# Patch_panel_module_-_CAT6_daughter_board.net
KiCad netlist of a schematic drawn in EAGLE
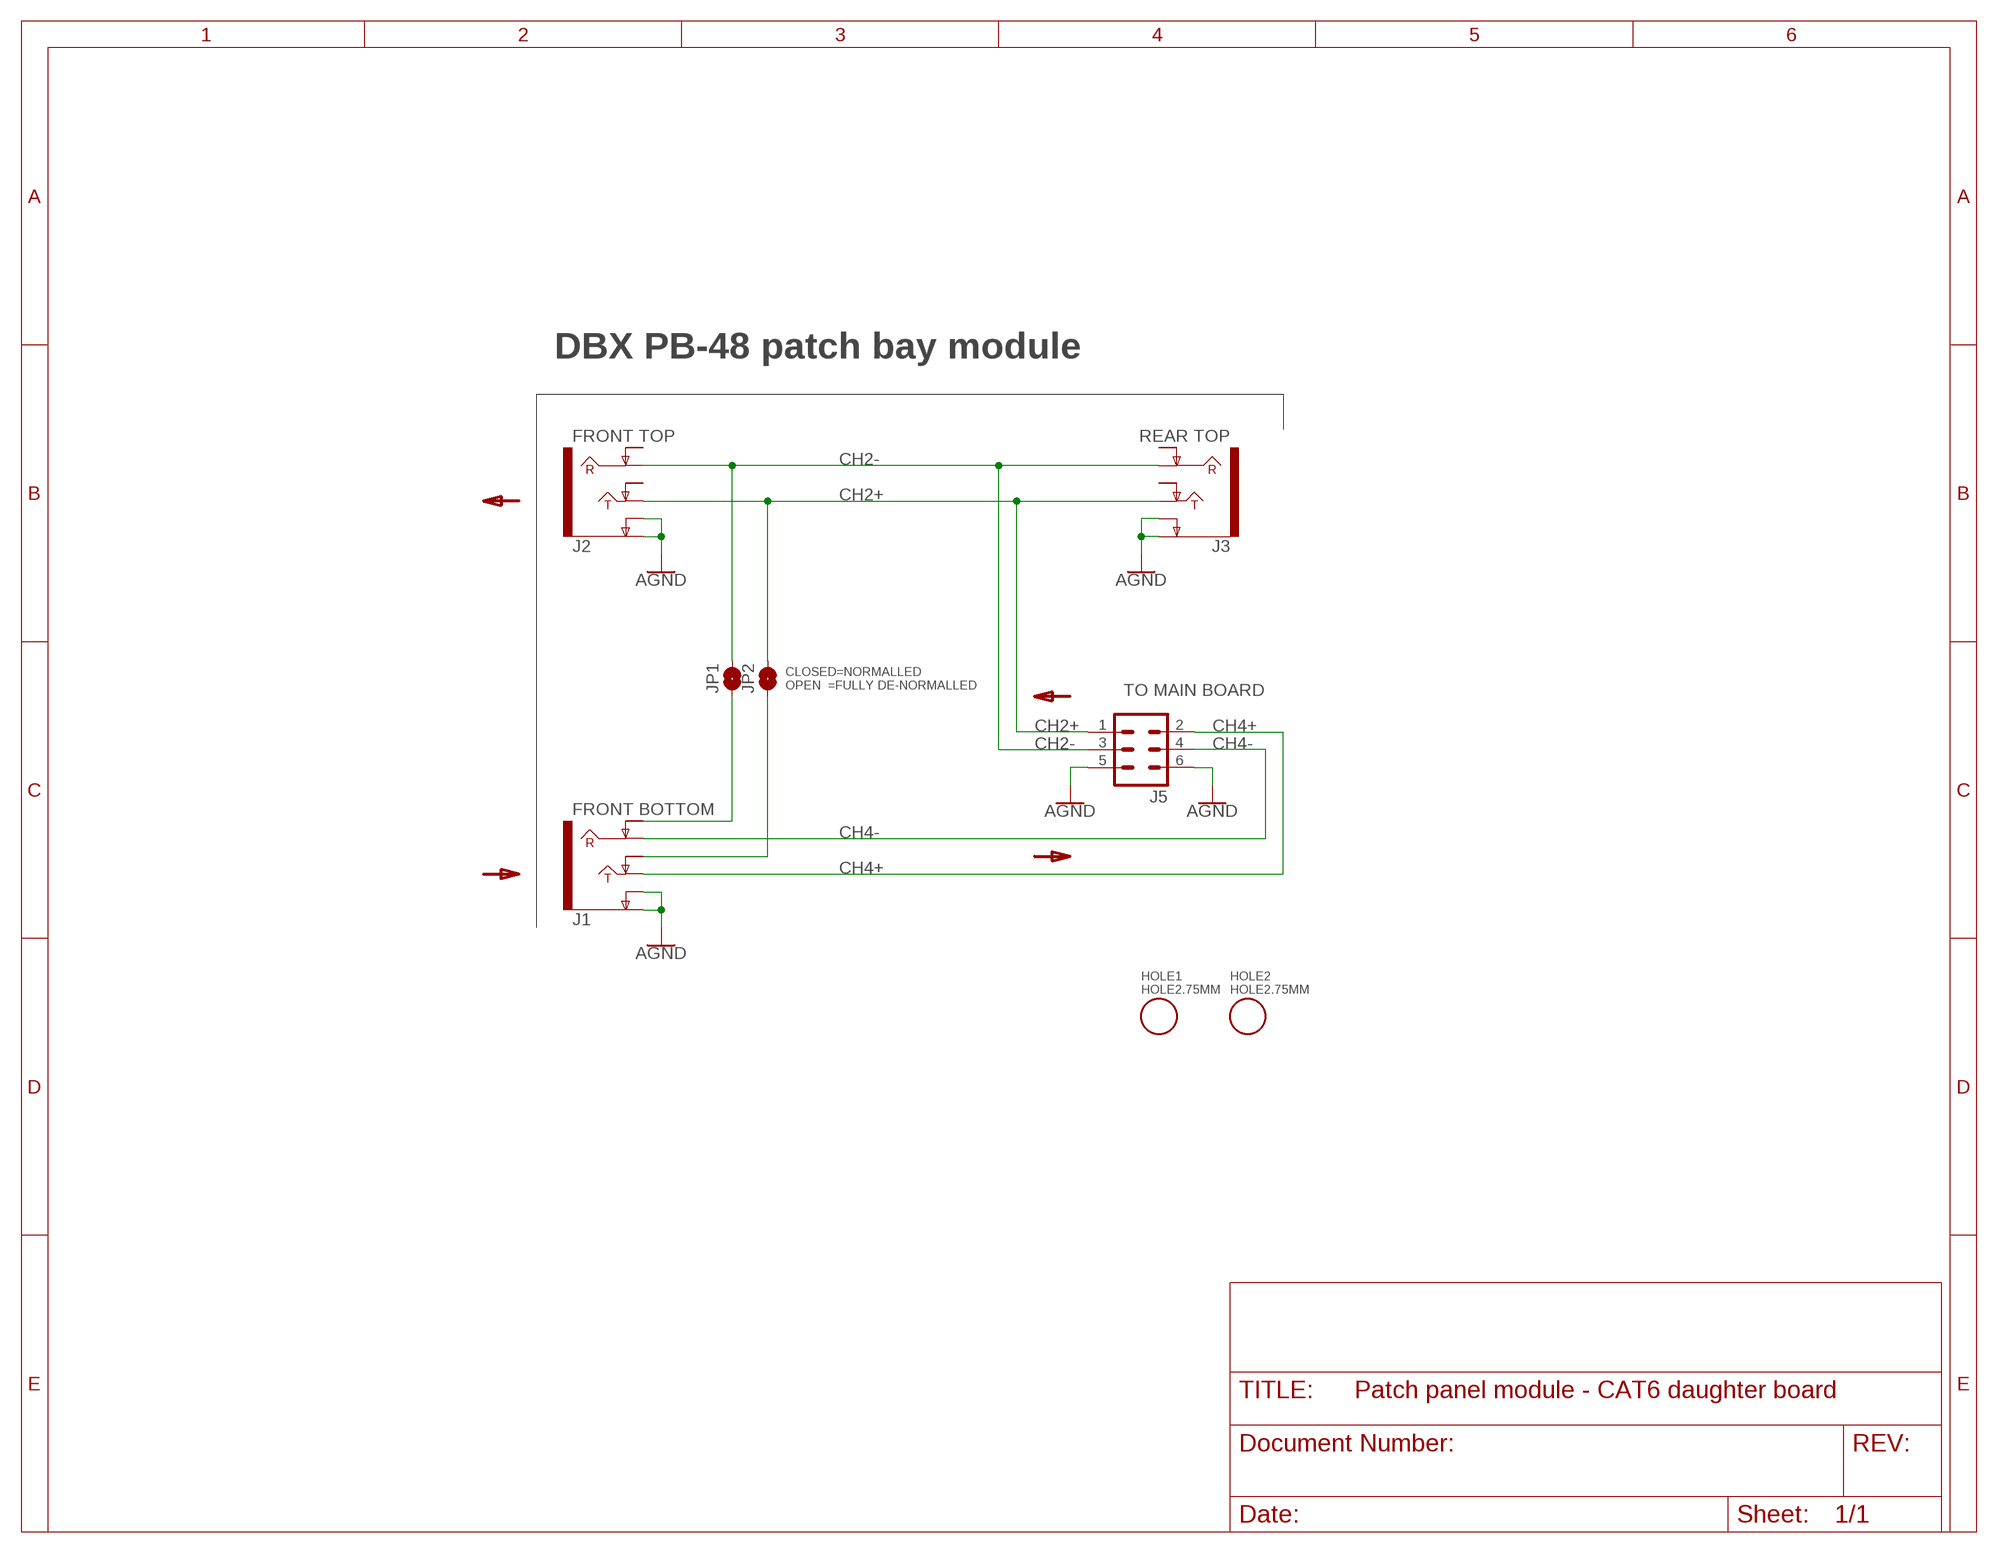
[diagram p0: schematic, sheet 1]

(export (version "E")
  (design (tool "Eeschema 10.0.6"))
  (components
    (comp (ref "HOLE1")
      (value "HOLE2.75MM")
      (footprint "eagle-import:HOLE-2.75MM")
      (libsource (lib "eagle-import") (part "HOLE2.75MM"))
    )
    (comp (ref "HOLE2")
      (value "HOLE2.75MM")
      (footprint "eagle-import:HOLE-2.75MM")
      (libsource (lib "eagle-import") (part "HOLE2.75MM"))
    )
    (comp (ref "J1")
      (value "FRONT BOTTOM")
      (footprint "eagle-import:NEUTRIK-NRJ6HF")
      (libsource (lib "eagle-import") (part "AUDIO_JACK_TRS_0.25{dblquote}_PTH_RA-NRJ6HM"))
    )
    (comp (ref "J2")
      (value "FRONT TOP")
      (footprint "eagle-import:NEUTRIK-NRJ6HF")
      (libsource (lib "eagle-import") (part "AUDIO_JACK_TRS_0.25{dblquote}_PTH_RA-NRJ6HM"))
    )
    (comp (ref "J3")
      (value "REAR TOP")
      (footprint "eagle-import:NEUTRIK-NRJ6HF")
      (libsource (lib "eagle-import") (part "AUDIO_JACK_TRS_0.25{dblquote}_PTH_RA-NRJ6HM"))
    )
    (comp (ref "J5")
      (value "MA03-2")
      (footprint "eagle-import:MA03-2")
      (libsource (lib "eagle-import") (part "MA03-2"))
    )
    (comp (ref "JP1")
      (value "JUMPER-SMT_2_NO_NO-SILK_ROUND")
      (footprint "eagle-import:SMT-JUMPER_2_NO_NO-SILK_ROUND")
      (libsource (lib "eagle-import") (part "JUMPER-SMT_2_NO_NO-SILK_ROUND"))
    )
    (comp (ref "JP2")
      (value "JUMPER-SMT_2_NO_NO-SILK_ROUND")
      (footprint "eagle-import:SMT-JUMPER_2_NO_NO-SILK_ROUND")
      (libsource (lib "eagle-import") (part "JUMPER-SMT_2_NO_NO-SILK_ROUND"))
    )
  )
  (nets
    (net (code "1") (name "/CH2+") (class "Default")
      (node (ref "J2") (pin "T") (pinfunction "TIP_T") (pintype "bidirectional"))
      (node (ref "J3") (pin "T") (pinfunction "TIP_T") (pintype "bidirectional"))
      (node (ref "J5") (pin "1") (pinfunction "1_1") (pintype "passive"))
      (node (ref "JP2") (pin "2") (pinfunction "2_2") (pintype "passive"))
    )
    (net (code "2") (name "/CH2-") (class "Default")
      (node (ref "J2") (pin "R") (pinfunction "RING_R") (pintype "bidirectional"))
      (node (ref "J3") (pin "R") (pinfunction "RING_R") (pintype "bidirectional"))
      (node (ref "J5") (pin "3") (pinfunction "3_3") (pintype "passive"))
      (node (ref "JP1") (pin "2") (pinfunction "2_2") (pintype "passive"))
    )
    (net (code "3") (name "/CH4+") (class "Default")
      (node (ref "J1") (pin "T") (pinfunction "TIP_T") (pintype "bidirectional"))
      (node (ref "J5") (pin "2") (pinfunction "2_2") (pintype "passive"))
    )
    (net (code "4") (name "/CH4-") (class "Default")
      (node (ref "J1") (pin "R") (pinfunction "RING_R") (pintype "bidirectional"))
      (node (ref "J5") (pin "4") (pinfunction "4_4") (pintype "passive"))
    )
    (net (code "5") (name "AGND") (class "Default")
      (node (ref "J1") (pin "S") (pinfunction "EARTH_S") (pintype "bidirectional"))
      (node (ref "J1") (pin "SN") (pinfunction "EARTH-NORM_SN") (pintype "bidirectional"))
      (node (ref "J2") (pin "S") (pinfunction "EARTH_S") (pintype "bidirectional"))
      (node (ref "J2") (pin "SN") (pinfunction "EARTH-NORM_SN") (pintype "bidirectional"))
      (node (ref "J3") (pin "S") (pinfunction "EARTH_S") (pintype "bidirectional"))
      (node (ref "J3") (pin "SN") (pinfunction "EARTH-NORM_SN") (pintype "bidirectional"))
      (node (ref "J5") (pin "5") (pinfunction "5_5") (pintype "passive"))
      (node (ref "J5") (pin "6") (pinfunction "6_6") (pintype "passive"))
    )
    (net (code "6") (name "Net-(J1-RING-NORM)") (class "Default")
      (node (ref "J1") (pin "RN") (pinfunction "RING-NORM_RN") (pintype "bidirectional"))
      (node (ref "JP1") (pin "1") (pinfunction "1_1") (pintype "passive"))
    )
    (net (code "7") (name "Net-(J1-TIP-NORM)") (class "Default")
      (node (ref "J1") (pin "TN") (pinfunction "TIP-NORM_TN") (pintype "bidirectional"))
      (node (ref "JP2") (pin "1") (pinfunction "1_1") (pintype "passive"))
    )
    (net (code "8") (name "unconnected-(J2-RING-NORM-PadRN)") (class "Default")
      (node (ref "J2") (pin "RN") (pinfunction "RING-NORM_RN") (pintype "bidirectional"))
    )
    (net (code "9") (name "unconnected-(J2-TIP-NORM-PadTN)") (class "Default")
      (node (ref "J2") (pin "TN") (pinfunction "TIP-NORM_TN") (pintype "bidirectional"))
    )
    (net (code "10") (name "unconnected-(J3-RING-NORM-PadRN)") (class "Default")
      (node (ref "J3") (pin "RN") (pinfunction "RING-NORM_RN") (pintype "bidirectional"))
    )
    (net (code "11") (name "unconnected-(J3-TIP-NORM-PadTN)") (class "Default")
      (node (ref "J3") (pin "TN") (pinfunction "TIP-NORM_TN") (pintype "bidirectional"))
    )
  )
)
